# Perifericos.net
KiCad netlist of a schematic drawn in Altium Designer
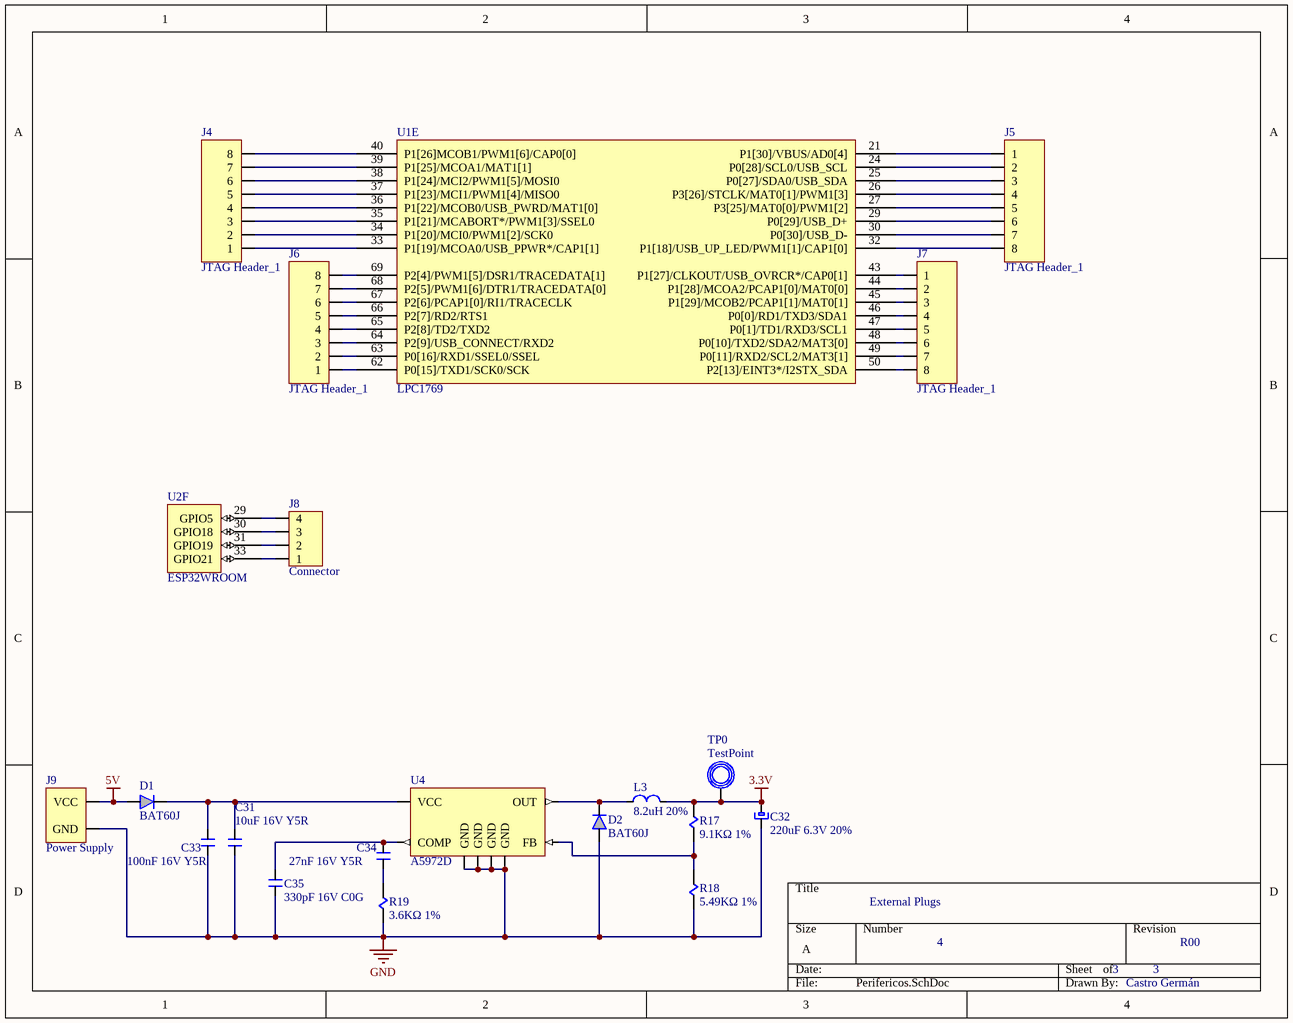
[diagram p0: Perifericos.SchDoc]

(export (version "E")
  (design (tool "Eeschema 10.0.6"))
  (components
    (comp (ref "C31")
      (value "10uF 16V Y5R")
      (footprint "C_0805")
      (description "Capacitor")
      (libsource (lib "MyPro") (part "Capacitor"))
    )
    (comp (ref "C32")
      (value "220uF 6.3V 20%")
      (footprint "CT_2917_D")
      (libsource (lib "MyPro") (part "Polarized Capacitor"))
    )
    (comp (ref "C33")
      (value "100nF 16V Y5R")
      (footprint "C_0805")
      (description "Capacitor")
      (libsource (lib "MyPro") (part "Capacitor"))
    )
    (comp (ref "C34")
      (value "27nF 16V Y5R")
      (footprint "C_0805")
      (description "Capacitor")
      (libsource (lib "MyPro") (part "Capacitor"))
    )
    (comp (ref "C35")
      (value "330pF 16V C0G")
      (footprint "C_0805")
      (description "Capacitor")
      (libsource (lib "MyPro") (part "Capacitor"))
    )
    (comp (ref "D1")
      (value "BAT60J")
      (footprint "SOD323")
      (description "Generic Diode")
      (libsource (lib "MyPro") (part "Diode"))
    )
    (comp (ref "D2")
      (value "BAT60J")
      (footprint "SOD323")
      (description "Generic Diode")
      (libsource (lib "MyPro") (part "Diode"))
    )
    (comp (ref "J4")
      (value "JTAG Header_1")
      (footprint "HDRM_2.54mm_1X8")
      (libsource (lib "MyPro") (part "Connector1x8"))
    )
    (comp (ref "J5")
      (value "JTAG Header_1")
      (footprint "HDRM_2.54mm_1X8")
      (libsource (lib "") (part "Connector1x8_1"))
    )
    (comp (ref "J6")
      (value "JTAG Header_1")
      (footprint "HDRM_2.54mm_1X8")
      (libsource (lib "MyPro") (part "Connector1x8"))
    )
    (comp (ref "J7")
      (value "JTAG Header_1")
      (footprint "HDRM_2.54mm_1X8")
      (libsource (lib "") (part "Connector1x8_1"))
    )
    (comp (ref "J8")
      (value "Connector")
      (footprint "HDRM_0.1_1X4")
      (libsource (lib "MyPro") (part "Connectorx4"))
    )
    (comp (ref "J9")
      (value "Power Supply")
      (footprint "HDRM_0.1_1x2")
      (libsource (lib "MyPro") (part "Power Connector"))
    )
    (comp (ref "L3")
      (value "8.2uH 20%")
      (footprint "1R5_1710")
      (description "Inductor")
      (libsource (lib "MyPro") (part "Inductor"))
    )
    (comp (ref "R17")
      (value "9.1KΩ 1%")
      (footprint "R_0805")
      (description "Resistor")
      (libsource (lib "MyPro") (part "Resistor"))
    )
    (comp (ref "R18")
      (value "5.49KΩ 1%")
      (footprint "R_0805")
      (description "Resistor")
      (libsource (lib "MyPro") (part "Resistor"))
    )
    (comp (ref "R19")
      (value "3.6KΩ 1%")
      (footprint "R_0805")
      (description "Resistor")
      (libsource (lib "MyPro") (part "Resistor"))
    )
    (comp (ref "TP0")
      (value "TestPoint")
      (footprint "TestPoint")
      (libsource (lib "MyPro") (part "TestPoint"))
    )
    (comp (ref "U1")
      (value "LPC1769")
      (footprint "LQFP100")
      (description "32 bit ARM Cortex M3")
      (libsource (lib "MyPro") (part "LPC1769"))
    )
    (comp (ref "U2")
      (value "ESP32WROOM")
      (footprint "ESP32_WROOM - duplicate")
      (libsource (lib "MyPro") (part "ESP32WROOM"))
    )
    (comp (ref "U4")
      (value "A5972D")
      (footprint "SO_8")
      (description "Fuente Switching 3.3v 1.5A")
      (libsource (lib "MyPro") (part "A5972D"))
    )
  )
  (nets
    (net (code "1") (name "3.3V") (class "Default")
      (node (ref "C32") (pin "1") (pinfunction "P_1") (pintype "passive"))
      (node (ref "L3") (pin "2") (pinfunction "P2_2") (pintype "passive"))
      (node (ref "R17") (pin "2") (pinfunction "P2_2") (pintype "passive"))
      (node (ref "TP0") (pin "1") (pinfunction "1_1") (pintype "passive"))
    )
    (net (code "2") (name "5V") (class "Default")
      (node (ref "D1") (pin "1") (pinfunction "A_1") (pintype "passive"))
      (node (ref "J9") (pin "1") (pinfunction "VCC_1") (pintype "passive"))
    )
    (net (code "3") (name "GND") (class "Default")
      (node (ref "C31") (pin "2") (pinfunction "A2_2") (pintype "passive"))
      (node (ref "C32") (pin "2") (pinfunction "N_2") (pintype "passive"))
      (node (ref "C33") (pin "2") (pinfunction "A2_2") (pintype "passive"))
      (node (ref "C35") (pin "2") (pinfunction "A2_2") (pintype "passive"))
      (node (ref "D2") (pin "1") (pinfunction "A_1") (pintype "passive"))
      (node (ref "J9") (pin "2") (pinfunction "GND_2") (pintype "passive"))
      (node (ref "R18") (pin "1") (pinfunction "P1_1") (pintype "passive"))
      (node (ref "R19") (pin "1") (pinfunction "P1_1") (pintype "passive"))
      (node (ref "U4") (pin "2") (pinfunction "GND_2") (pintype "passive"))
      (node (ref "U4") (pin "3") (pinfunction "GND_3") (pintype "passive"))
      (node (ref "U4") (pin "6") (pinfunction "GND_6") (pintype "passive"))
      (node (ref "U4") (pin "7") (pinfunction "GND_7") (pintype "passive"))
    )
    (net (code "4") (name "Net-(C31-A1)") (class "Default")
      (node (ref "C31") (pin "1") (pinfunction "A1_1") (pintype "passive"))
      (node (ref "C33") (pin "1") (pinfunction "A1_1") (pintype "passive"))
      (node (ref "D1") (pin "2") (pinfunction "K_2") (pintype "passive"))
      (node (ref "U4") (pin "8") (pinfunction "VCC_8") (pintype "passive"))
    )
    (net (code "5") (name "Net-(C34-A1)") (class "Default")
      (node (ref "C34") (pin "1") (pinfunction "A1_1") (pintype "passive"))
      (node (ref "C35") (pin "1") (pinfunction "A1_1") (pintype "passive"))
      (node (ref "U4") (pin "4") (pinfunction "COMP_4") (pintype "output"))
    )
    (net (code "6") (name "Net-(C34-A2)") (class "Default")
      (node (ref "C34") (pin "2") (pinfunction "A2_2") (pintype "passive"))
      (node (ref "R19") (pin "2") (pinfunction "P2_2") (pintype "passive"))
    )
    (net (code "7") (name "Net-(D2-K)") (class "Default")
      (node (ref "D2") (pin "2") (pinfunction "K_2") (pintype "passive"))
      (node (ref "L3") (pin "1") (pinfunction "P1_1") (pintype "passive"))
      (node (ref "U4") (pin "1") (pinfunction "OUT_1") (pintype "output"))
    )
    (net (code "8") (name "Net-(R17-P1)") (class "Default")
      (node (ref "R17") (pin "1") (pinfunction "P1_1") (pintype "passive"))
      (node (ref "R18") (pin "2") (pinfunction "P2_2") (pintype "passive"))
      (node (ref "U4") (pin "5") (pinfunction "FB_5") (pintype "input"))
    )
    (net (code "9") (name "Net-(U1E-P0[0]{slash}RD1{slash}TXD3{slash}SDA1)") (class "Default")
      (node (ref "J7") (pin "4") (pinfunction "4_4") (pintype "passive"))
      (node (ref "U1") (pin "46") (pinfunction "P0[0]/RD1/TXD3/SDA1_46") (pintype "passive"))
    )
    (net (code "10") (name "Net-(U1E-P0[1]{slash}TD1{slash}RXD3{slash}SCL1)") (class "Default")
      (node (ref "J7") (pin "5") (pinfunction "5_5") (pintype "passive"))
      (node (ref "U1") (pin "47") (pinfunction "P0[1]/TD1/RXD3/SCL1_47") (pintype "passive"))
    )
    (net (code "11") (name "Net-(U1E-P0[10]{slash}TXD2{slash}SDA2{slash}MAT3[0])") (class "Default")
      (node (ref "J7") (pin "6") (pinfunction "6_6") (pintype "passive"))
      (node (ref "U1") (pin "48") (pinfunction "P0[10]/TXD2/SDA2/MAT3[0]_48") (pintype "passive"))
    )
    (net (code "12") (name "Net-(U1E-P0[11]{slash}RXD2{slash}SCL2{slash}MAT3[1])") (class "Default")
      (node (ref "J7") (pin "7") (pinfunction "7_7") (pintype "passive"))
      (node (ref "U1") (pin "49") (pinfunction "P0[11]/RXD2/SCL2/MAT3[1]_49") (pintype "passive"))
    )
    (net (code "13") (name "Net-(U1E-P0[15]{slash}TXD1{slash}SCK0{slash}SCK)") (class "Default")
      (node (ref "J6") (pin "1") (pinfunction "1_1") (pintype "passive"))
      (node (ref "U1") (pin "62") (pinfunction "P0[15]/TXD1/SCK0/SCK_62") (pintype "passive"))
    )
    (net (code "14") (name "Net-(U1E-P0[16]{slash}RXD1{slash}SSEL0{slash}SSEL)") (class "Default")
      (node (ref "J6") (pin "2") (pinfunction "2_2") (pintype "passive"))
      (node (ref "U1") (pin "63") (pinfunction "P0[16]/RXD1/SSEL0/SSEL_63") (pintype "passive"))
    )
    (net (code "15") (name "Net-(U1E-P0[27]{slash}SDA0{slash}USB_SDA)") (class "Default")
      (node (ref "J5") (pin "3") (pinfunction "3_3") (pintype "passive"))
      (node (ref "U1") (pin "25") (pinfunction "P0[27]/SDA0/USB_SDA_25") (pintype "passive"))
    )
    (net (code "16") (name "Net-(U1E-P0[28]{slash}SCL0{slash}USB_SCL)") (class "Default")
      (node (ref "J5") (pin "2") (pinfunction "2_2") (pintype "passive"))
      (node (ref "U1") (pin "24") (pinfunction "P0[28]/SCL0/USB_SCL_24") (pintype "passive"))
    )
    (net (code "17") (name "Net-(U1E-P0[29]{slash}USB_D+)") (class "Default")
      (node (ref "J5") (pin "6") (pinfunction "6_6") (pintype "passive"))
      (node (ref "U1") (pin "29") (pinfunction "P0[29]/USB_D+_29") (pintype "passive"))
    )
    (net (code "18") (name "Net-(U1E-P0[30]{slash}USB_D-)") (class "Default")
      (node (ref "J5") (pin "7") (pinfunction "7_7") (pintype "passive"))
      (node (ref "U1") (pin "30") (pinfunction "P0[30]/USB_D-_30") (pintype "passive"))
    )
    (net (code "19") (name "Net-(U1E-P1[18]{slash}USB_UP_LED{slash}PWM1[1]{slash}CAP1[0])") (class "Default")
      (node (ref "J5") (pin "8") (pinfunction "8_8") (pintype "passive"))
      (node (ref "U1") (pin "32") (pinfunction "P1[18]/USB_UP_LED/PWM1[1]/CAP1[0]_32") (pintype "passive"))
    )
    (net (code "20") (name "Net-(U1E-P1[19]{slash}MCOA0{slash}USB_PPWR*{slash}CAP1[1])") (class "Default")
      (node (ref "J4") (pin "1") (pinfunction "1_1") (pintype "passive"))
      (node (ref "U1") (pin "33") (pinfunction "P1[19]/MCOA0/USB_PPWR*/CAP1[1]_33") (pintype "passive"))
    )
    (net (code "21") (name "Net-(U1E-P1[20]{slash}MCI0{slash}PWM1[2]{slash}SCK0)") (class "Default")
      (node (ref "J4") (pin "2") (pinfunction "2_2") (pintype "passive"))
      (node (ref "U1") (pin "34") (pinfunction "P1[20]/MCI0/PWM1[2]/SCK0_34") (pintype "passive"))
    )
    (net (code "22") (name "Net-(U1E-P1[21]{slash}MCABORT*{slash}PWM1[3]{slash}SSEL0)") (class "Default")
      (node (ref "J4") (pin "3") (pinfunction "3_3") (pintype "passive"))
      (node (ref "U1") (pin "35") (pinfunction "P1[21]/MCABORT*/PWM1[3]/SSEL0_35") (pintype "passive"))
    )
    (net (code "23") (name "Net-(U1E-P1[22]{slash}MCOB0{slash}USB_PWRD{slash}MAT1[0])") (class "Default")
      (node (ref "J4") (pin "4") (pinfunction "4_4") (pintype "passive"))
      (node (ref "U1") (pin "36") (pinfunction "P1[22]/MCOB0/USB_PWRD/MAT1[0]_36") (pintype "passive"))
    )
    (net (code "24") (name "Net-(U1E-P1[23]{slash}MCI1{slash}PWM1[4]{slash}MISO0)") (class "Default")
      (node (ref "J4") (pin "5") (pinfunction "5_5") (pintype "passive"))
      (node (ref "U1") (pin "37") (pinfunction "P1[23]/MCI1/PWM1[4]/MISO0_37") (pintype "passive"))
    )
    (net (code "25") (name "Net-(U1E-P1[24]{slash}MCI2{slash}PWM1[5]{slash}MOSI0)") (class "Default")
      (node (ref "J4") (pin "6") (pinfunction "6_6") (pintype "passive"))
      (node (ref "U1") (pin "38") (pinfunction "P1[24]/MCI2/PWM1[5]/MOSI0_38") (pintype "passive"))
    )
    (net (code "26") (name "Net-(U1E-P1[25]{slash}MCOA1{slash}MAT1[1])") (class "Default")
      (node (ref "J4") (pin "7") (pinfunction "7_7") (pintype "passive"))
      (node (ref "U1") (pin "39") (pinfunction "P1[25]/MCOA1/MAT1[1]_39") (pintype "passive"))
    )
    (net (code "27") (name "Net-(U1E-P1[26]MCOB1{slash}PWM1[6]{slash}CAP0[0])") (class "Default")
      (node (ref "J4") (pin "8") (pinfunction "8_8") (pintype "passive"))
      (node (ref "U1") (pin "40") (pinfunction "P1[26]MCOB1/PWM1[6]/CAP0[0]_40") (pintype "passive"))
    )
    (net (code "28") (name "Net-(U1E-P1[27]{slash}CLKOUT{slash}USB_OVRCR*{slash}CAP0[1])") (class "Default")
      (node (ref "J7") (pin "1") (pinfunction "1_1") (pintype "passive"))
      (node (ref "U1") (pin "43") (pinfunction "P1[27]/CLKOUT/USB_OVRCR*/CAP0[1]_43") (pintype "passive"))
    )
    (net (code "29") (name "Net-(U1E-P1[28]{slash}MCOA2{slash}PCAP1[0]{slash}MAT0[0])") (class "Default")
      (node (ref "J7") (pin "2") (pinfunction "2_2") (pintype "passive"))
      (node (ref "U1") (pin "44") (pinfunction "P1[28]/MCOA2/PCAP1[0]/MAT0[0]_44") (pintype "passive"))
    )
    (net (code "30") (name "Net-(U1E-P1[29]{slash}MCOB2{slash}PCAP1[1]{slash}MAT0[1])") (class "Default")
      (node (ref "J7") (pin "3") (pinfunction "3_3") (pintype "passive"))
      (node (ref "U1") (pin "45") (pinfunction "P1[29]/MCOB2/PCAP1[1]/MAT0[1]_45") (pintype "passive"))
    )
    (net (code "31") (name "Net-(U1E-P1[30]{slash}VBUS{slash}AD0[4])") (class "Default")
      (node (ref "J5") (pin "1") (pinfunction "1_1") (pintype "passive"))
      (node (ref "U1") (pin "21") (pinfunction "P1[30]/VBUS/AD0[4]_21") (pintype "passive"))
    )
    (net (code "32") (name "Net-(U1E-P2[4]{slash}PWM1[5]{slash}DSR1{slash}TRACEDATA[1])") (class "Default")
      (node (ref "J6") (pin "8") (pinfunction "8_8") (pintype "passive"))
      (node (ref "U1") (pin "69") (pinfunction "P2[4]/PWM1[5]/DSR1/TRACEDATA[1]_69") (pintype "passive"))
    )
    (net (code "33") (name "Net-(U1E-P2[5]{slash}PWM1[6]{slash}DTR1{slash}TRACEDATA[0])") (class "Default")
      (node (ref "J6") (pin "7") (pinfunction "7_7") (pintype "passive"))
      (node (ref "U1") (pin "68") (pinfunction "P2[5]/PWM1[6]/DTR1/TRACEDATA[0]_68") (pintype "passive"))
    )
    (net (code "34") (name "Net-(U1E-P2[6]{slash}PCAP1[0]{slash}RI1{slash}TRACECLK)") (class "Default")
      (node (ref "J6") (pin "6") (pinfunction "6_6") (pintype "passive"))
      (node (ref "U1") (pin "67") (pinfunction "P2[6]/PCAP1[0]/RI1/TRACECLK_67") (pintype "passive"))
    )
    (net (code "35") (name "Net-(U1E-P2[7]{slash}RD2{slash}RTS1)") (class "Default")
      (node (ref "J6") (pin "5") (pinfunction "5_5") (pintype "passive"))
      (node (ref "U1") (pin "66") (pinfunction "P2[7]/RD2/RTS1_66") (pintype "passive"))
    )
    (net (code "36") (name "Net-(U1E-P2[8]{slash}TD2{slash}TXD2)") (class "Default")
      (node (ref "J6") (pin "4") (pinfunction "4_4") (pintype "passive"))
      (node (ref "U1") (pin "65") (pinfunction "P2[8]/TD2/TXD2_65") (pintype "passive"))
    )
    (net (code "37") (name "Net-(U1E-P2[9]{slash}USB_CONNECT{slash}RXD2)") (class "Default")
      (node (ref "J6") (pin "3") (pinfunction "3_3") (pintype "passive"))
      (node (ref "U1") (pin "64") (pinfunction "P2[9]/USB_CONNECT/RXD2_64") (pintype "passive"))
    )
    (net (code "38") (name "Net-(U1E-P2[13]{slash}EINT3*{slash}I2STX_SDA)") (class "Default")
      (node (ref "J7") (pin "8") (pinfunction "8_8") (pintype "passive"))
      (node (ref "U1") (pin "50") (pinfunction "P2[13]/EINT3*/I2STX_SDA_50") (pintype "passive"))
    )
    (net (code "39") (name "Net-(U1E-P3[25]{slash}MAT0[0]{slash}PWM1[2])") (class "Default")
      (node (ref "J5") (pin "5") (pinfunction "5_5") (pintype "passive"))
      (node (ref "U1") (pin "27") (pinfunction "P3[25]/MAT0[0]/PWM1[2]_27") (pintype "passive"))
    )
    (net (code "40") (name "Net-(U1E-P3[26]{slash}STCLK{slash}MAT0[1]{slash}PWM1[3])") (class "Default")
      (node (ref "J5") (pin "4") (pinfunction "4_4") (pintype "passive"))
      (node (ref "U1") (pin "26") (pinfunction "P3[26]/STCLK/MAT0[1]/PWM1[3]_26") (pintype "passive"))
    )
    (net (code "41") (name "Net-(U2F-GPIO5)") (class "Default")
      (node (ref "J8") (pin "4") (pinfunction "4_4") (pintype "passive"))
      (node (ref "U2") (pin "29") (pinfunction "GPIO5_29") (pintype "bidirectional"))
    )
    (net (code "42") (name "Net-(U2F-GPIO18)") (class "Default")
      (node (ref "J8") (pin "3") (pinfunction "3_3") (pintype "passive"))
      (node (ref "U2") (pin "30") (pinfunction "GPIO18_30") (pintype "bidirectional"))
    )
    (net (code "43") (name "Net-(U2F-GPIO19)") (class "Default")
      (node (ref "J8") (pin "2") (pinfunction "2_2") (pintype "passive"))
      (node (ref "U2") (pin "31") (pinfunction "GPIO19_31") (pintype "bidirectional"))
    )
    (net (code "44") (name "Net-(U2F-GPIO21)") (class "Default")
      (node (ref "J8") (pin "1") (pinfunction "1_1") (pintype "passive"))
      (node (ref "U2") (pin "33") (pinfunction "GPIO21_33") (pintype "bidirectional"))
    )
  )
)
